# Microcontroller.net
KiCad netlist of a schematic drawn in Altium Designer
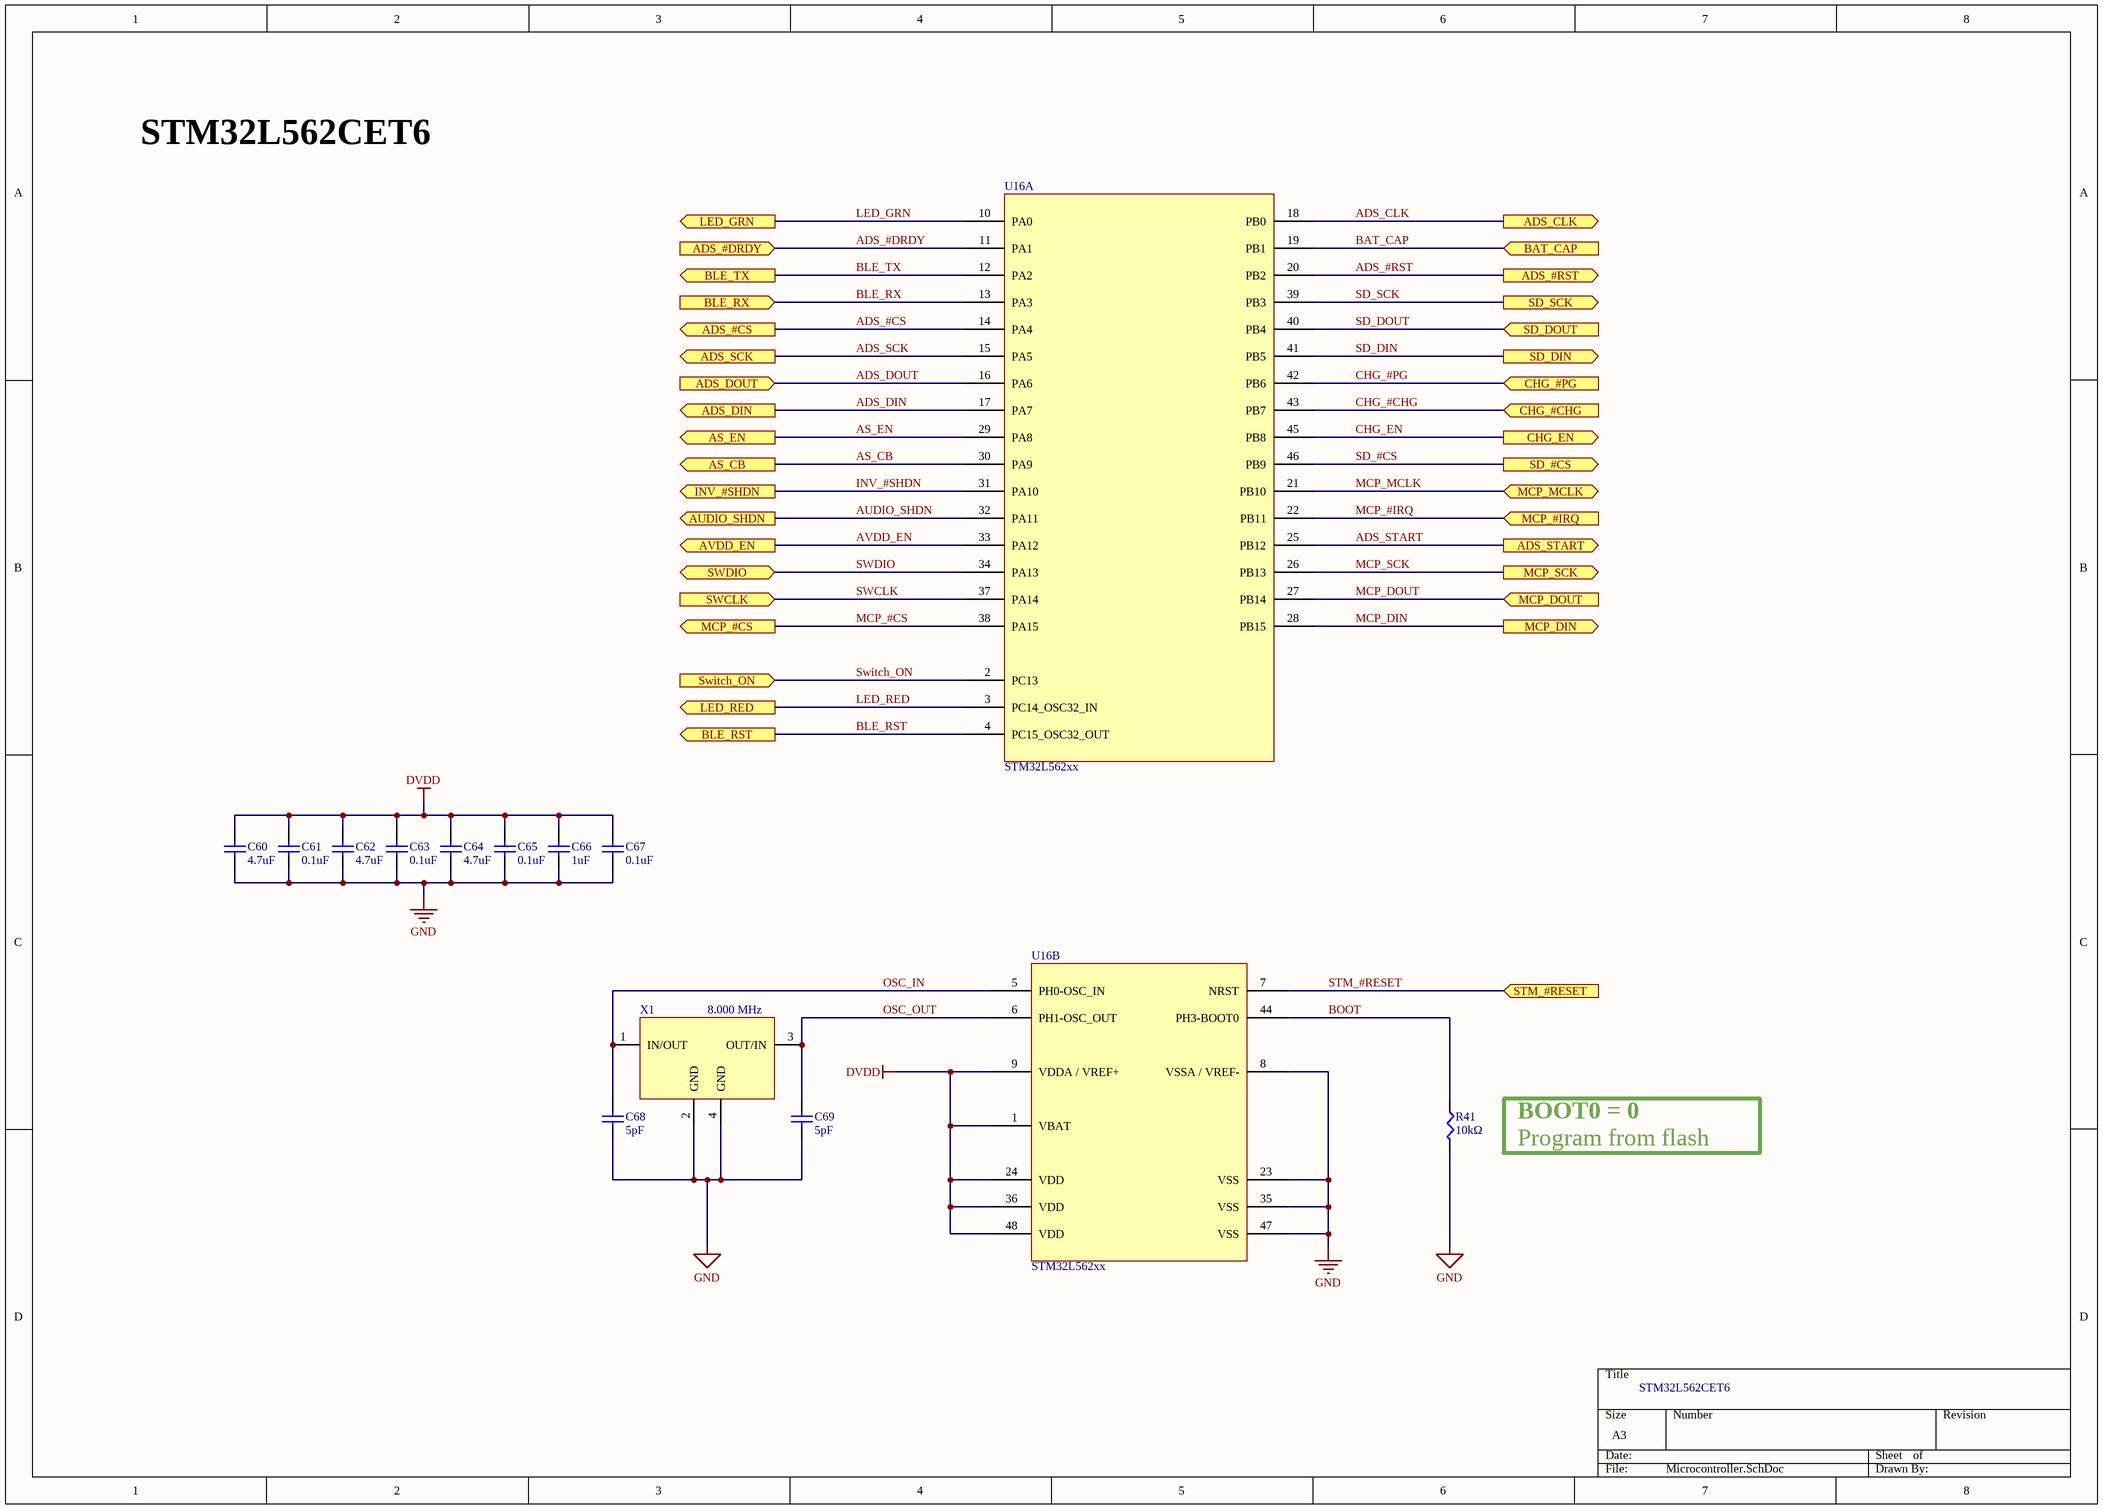
[diagram p0: Microcontroller.SchDoc]

(export (version "E")
  (design (tool "Eeschema 10.0.6"))
  (components
    (comp (ref "C60")
      (value "4.7uF")
      (footprint "0603")
      (description "MLCC-0603")
      (libsource (lib "MLCC") (part "0603"))
    )
    (comp (ref "C61")
      (value "0.1uF")
      (footprint "0402")
      (description "MLCC-0402")
      (libsource (lib "MLCC") (part "0402"))
    )
    (comp (ref "C62")
      (value "4.7uF")
      (footprint "0603")
      (description "MLCC-0603")
      (libsource (lib "MLCC") (part "0603"))
    )
    (comp (ref "C63")
      (value "0.1uF")
      (footprint "0402")
      (description "MLCC-0402")
      (libsource (lib "MLCC") (part "0402"))
    )
    (comp (ref "C64")
      (value "4.7uF")
      (footprint "0603")
      (description "MLCC-0603")
      (libsource (lib "MLCC") (part "0603"))
    )
    (comp (ref "C65")
      (value "0.1uF")
      (footprint "0402")
      (description "MLCC-0402")
      (libsource (lib "MLCC") (part "0402"))
    )
    (comp (ref "C66")
      (value "1uF")
      (footprint "0402")
      (description "MLCC-0402")
      (libsource (lib "MLCC") (part "0402"))
    )
    (comp (ref "C67")
      (value "0.1uF")
      (footprint "0402")
      (description "MLCC-0402")
      (libsource (lib "MLCC") (part "0402"))
    )
    (comp (ref "C68")
      (value "5pF")
      (footprint "0402")
      (description "MLCC-0402")
      (libsource (lib "MLCC") (part "0402"))
    )
    (comp (ref "C69")
      (value "5pF")
      (footprint "0402")
      (description "MLCC-0402")
      (libsource (lib "MLCC") (part "0402"))
    )
    (comp (ref "R41")
      (value "10kΩ")
      (footprint "0402")
      (description "Resistor_SMD_0402")
      (fields (field (name "AUTHORBY") "yjlab"))
      (libsource (lib "Resistor") (part "0402"))
    )
    (comp (ref "U16")
      (value "STM32L562xx")
      (footprint "LQFP48")
      (description "STM32, 32 Bit MCU, 48 Pin, Arm Cortex-M33, 512 (kB) Flash, 256 (kB) SRAM")
      (libsource (lib "STM32L562xx") (part "STM32L562xx"))
    )
    (comp (ref "X1")
      (value "8.000 MHz")
      (footprint "SMD-4")
      (description "Crystals ECX-53B 8.000 MHz 10 pF")
      (libsource (lib "ECX-53B") (part "ECS-80-10-30B-CKM-TR"))
    )
  )
  (nets
    (net (code "1") (name "/ADS_#CS") (class "Default")
      (node (ref "U16") (pin "14") (pinfunction "PA4_14") (pintype "passive"))
    )
    (net (code "2") (name "/ADS_#DRDY") (class "Default")
      (node (ref "U16") (pin "11") (pinfunction "PA1_11") (pintype "passive"))
    )
    (net (code "3") (name "/ADS_#RST") (class "Default")
      (node (ref "U16") (pin "20") (pinfunction "PB2_20") (pintype "passive"))
    )
    (net (code "4") (name "/ADS_CLK") (class "Default")
      (node (ref "U16") (pin "18") (pinfunction "PB0_18") (pintype "passive"))
    )
    (net (code "5") (name "/ADS_DIN") (class "Default")
      (node (ref "U16") (pin "17") (pinfunction "PA7_17") (pintype "passive"))
    )
    (net (code "6") (name "/ADS_DOUT") (class "Default")
      (node (ref "U16") (pin "16") (pinfunction "PA6_16") (pintype "passive"))
    )
    (net (code "7") (name "/ADS_SCK") (class "Default")
      (node (ref "U16") (pin "15") (pinfunction "PA5_15") (pintype "passive"))
    )
    (net (code "8") (name "/ADS_START") (class "Default")
      (node (ref "U16") (pin "25") (pinfunction "PB12_25") (pintype "passive"))
    )
    (net (code "9") (name "/AS_CB") (class "Default")
      (node (ref "U16") (pin "30") (pinfunction "PA9_30") (pintype "passive"))
    )
    (net (code "10") (name "/AS_EN") (class "Default")
      (node (ref "U16") (pin "29") (pinfunction "PA8_29") (pintype "passive"))
    )
    (net (code "11") (name "/AUDIO_SHDN") (class "Default")
      (node (ref "U16") (pin "32") (pinfunction "PA11_32") (pintype "passive"))
    )
    (net (code "12") (name "/AVDD_EN") (class "Default")
      (node (ref "U16") (pin "33") (pinfunction "PA12_33") (pintype "passive"))
    )
    (net (code "13") (name "/BAT_CAP") (class "Default")
      (node (ref "U16") (pin "19") (pinfunction "PB1_19") (pintype "passive"))
    )
    (net (code "14") (name "/BLE_RST") (class "Default")
      (node (ref "U16") (pin "4") (pinfunction "PC15_OSC32_OUT_4") (pintype "passive"))
    )
    (net (code "15") (name "/BLE_RX") (class "Default")
      (node (ref "U16") (pin "13") (pinfunction "PA3_13") (pintype "passive"))
    )
    (net (code "16") (name "/BLE_TX") (class "Default")
      (node (ref "U16") (pin "12") (pinfunction "PA2_12") (pintype "passive"))
    )
    (net (code "17") (name "/BOOT") (class "Default")
      (node (ref "R41") (pin "1") (pinfunction "1_1") (pintype "passive"))
      (node (ref "U16") (pin "44") (pinfunction "PH3-BOOT0_44") (pintype "passive"))
    )
    (net (code "18") (name "/CHG_#CHG") (class "Default")
      (node (ref "U16") (pin "43") (pinfunction "PB7_43") (pintype "passive"))
    )
    (net (code "19") (name "/CHG_#PG") (class "Default")
      (node (ref "U16") (pin "42") (pinfunction "PB6_42") (pintype "passive"))
    )
    (net (code "20") (name "/CHG_EN") (class "Default")
      (node (ref "U16") (pin "45") (pinfunction "PB8_45") (pintype "passive"))
    )
    (net (code "21") (name "/INV_#SHDN") (class "Default")
      (node (ref "U16") (pin "31") (pinfunction "PA10_31") (pintype "passive"))
    )
    (net (code "22") (name "/LED_GRN") (class "Default")
      (node (ref "U16") (pin "10") (pinfunction "PA0_10") (pintype "passive"))
    )
    (net (code "23") (name "/LED_RED") (class "Default")
      (node (ref "U16") (pin "3") (pinfunction "PC14_OSC32_IN_3") (pintype "passive"))
    )
    (net (code "24") (name "/MCP_#CS") (class "Default")
      (node (ref "U16") (pin "38") (pinfunction "PA15_38") (pintype "passive"))
    )
    (net (code "25") (name "/MCP_#IRQ") (class "Default")
      (node (ref "U16") (pin "22") (pinfunction "PB11_22") (pintype "passive"))
    )
    (net (code "26") (name "/MCP_DIN") (class "Default")
      (node (ref "U16") (pin "28") (pinfunction "PB15_28") (pintype "passive"))
    )
    (net (code "27") (name "/MCP_DOUT") (class "Default")
      (node (ref "U16") (pin "27") (pinfunction "PB14_27") (pintype "passive"))
    )
    (net (code "28") (name "/MCP_MCLK") (class "Default")
      (node (ref "U16") (pin "21") (pinfunction "PB10_21") (pintype "passive"))
    )
    (net (code "29") (name "/MCP_SCK") (class "Default")
      (node (ref "U16") (pin "26") (pinfunction "PB13_26") (pintype "passive"))
    )
    (net (code "30") (name "/OSC_IN") (class "Default")
      (node (ref "C68") (pin "2") (pinfunction "2_2") (pintype "passive"))
      (node (ref "U16") (pin "5") (pinfunction "PH0-OSC_IN_5") (pintype "passive"))
      (node (ref "X1") (pin "1") (pinfunction "IN/OUT_1") (pintype "passive"))
    )
    (net (code "31") (name "/OSC_OUT") (class "Default")
      (node (ref "C69") (pin "2") (pinfunction "2_2") (pintype "passive"))
      (node (ref "U16") (pin "6") (pinfunction "PH1-OSC_OUT_6") (pintype "passive"))
      (node (ref "X1") (pin "3") (pinfunction "OUT/IN_3") (pintype "passive"))
    )
    (net (code "32") (name "/SD_#CS") (class "Default")
      (node (ref "U16") (pin "46") (pinfunction "PB9_46") (pintype "passive"))
    )
    (net (code "33") (name "/SD_DIN") (class "Default")
      (node (ref "U16") (pin "41") (pinfunction "PB5_41") (pintype "passive"))
    )
    (net (code "34") (name "/SD_DOUT") (class "Default")
      (node (ref "U16") (pin "40") (pinfunction "PB4_40") (pintype "passive"))
    )
    (net (code "35") (name "/SD_SCK") (class "Default")
      (node (ref "U16") (pin "39") (pinfunction "PB3_39") (pintype "passive"))
    )
    (net (code "36") (name "/STM_#RESET") (class "Default")
      (node (ref "U16") (pin "7") (pinfunction "NRST_7") (pintype "passive"))
    )
    (net (code "37") (name "/SWCLK") (class "Default")
      (node (ref "U16") (pin "37") (pinfunction "PA14_37") (pintype "passive"))
    )
    (net (code "38") (name "/SWDIO") (class "Default")
      (node (ref "U16") (pin "34") (pinfunction "PA13_34") (pintype "passive"))
    )
    (net (code "39") (name "/Switch_ON") (class "Default")
      (node (ref "U16") (pin "2") (pinfunction "PC13_2") (pintype "passive"))
    )
    (net (code "40") (name "DVDD") (class "Default")
      (node (ref "C60") (pin "2") (pinfunction "2_2") (pintype "passive"))
      (node (ref "C61") (pin "2") (pinfunction "2_2") (pintype "passive"))
      (node (ref "C62") (pin "2") (pinfunction "2_2") (pintype "passive"))
      (node (ref "C63") (pin "2") (pinfunction "2_2") (pintype "passive"))
      (node (ref "C64") (pin "2") (pinfunction "2_2") (pintype "passive"))
      (node (ref "C65") (pin "2") (pinfunction "2_2") (pintype "passive"))
      (node (ref "C66") (pin "2") (pinfunction "2_2") (pintype "passive"))
      (node (ref "C67") (pin "2") (pinfunction "2_2") (pintype "passive"))
      (node (ref "U16") (pin "1") (pinfunction "VBAT_1") (pintype "passive"))
      (node (ref "U16") (pin "24") (pinfunction "VDD_24") (pintype "passive"))
      (node (ref "U16") (pin "36") (pinfunction "VDD_36") (pintype "passive"))
      (node (ref "U16") (pin "48") (pinfunction "VDD_48") (pintype "passive"))
      (node (ref "U16") (pin "9") (pinfunction "VDDA_/_VREF+_9") (pintype "passive"))
    )
    (net (code "41") (name "GND") (class "Default")
      (node (ref "C60") (pin "1") (pinfunction "1_1") (pintype "passive"))
      (node (ref "C61") (pin "1") (pinfunction "1_1") (pintype "passive"))
      (node (ref "C62") (pin "1") (pinfunction "1_1") (pintype "passive"))
      (node (ref "C63") (pin "1") (pinfunction "1_1") (pintype "passive"))
      (node (ref "C64") (pin "1") (pinfunction "1_1") (pintype "passive"))
      (node (ref "C65") (pin "1") (pinfunction "1_1") (pintype "passive"))
      (node (ref "C66") (pin "1") (pinfunction "1_1") (pintype "passive"))
      (node (ref "C67") (pin "1") (pinfunction "1_1") (pintype "passive"))
      (node (ref "C68") (pin "1") (pinfunction "1_1") (pintype "passive"))
      (node (ref "C69") (pin "1") (pinfunction "1_1") (pintype "passive"))
      (node (ref "R41") (pin "2") (pinfunction "2_2") (pintype "passive"))
      (node (ref "U16") (pin "23") (pinfunction "VSS_23") (pintype "passive"))
      (node (ref "U16") (pin "35") (pinfunction "VSS_35") (pintype "passive"))
      (node (ref "U16") (pin "47") (pinfunction "VSS_47") (pintype "passive"))
      (node (ref "U16") (pin "8") (pinfunction "VSSA_/_VREF-_8") (pintype "passive"))
      (node (ref "X1") (pin "2") (pinfunction "GND_2") (pintype "passive"))
      (node (ref "X1") (pin "4") (pinfunction "GND_4") (pintype "passive"))
    )
  )
)
